# logic_qspi.net
KiCad netlist of a schematic drawn in Altium Designer
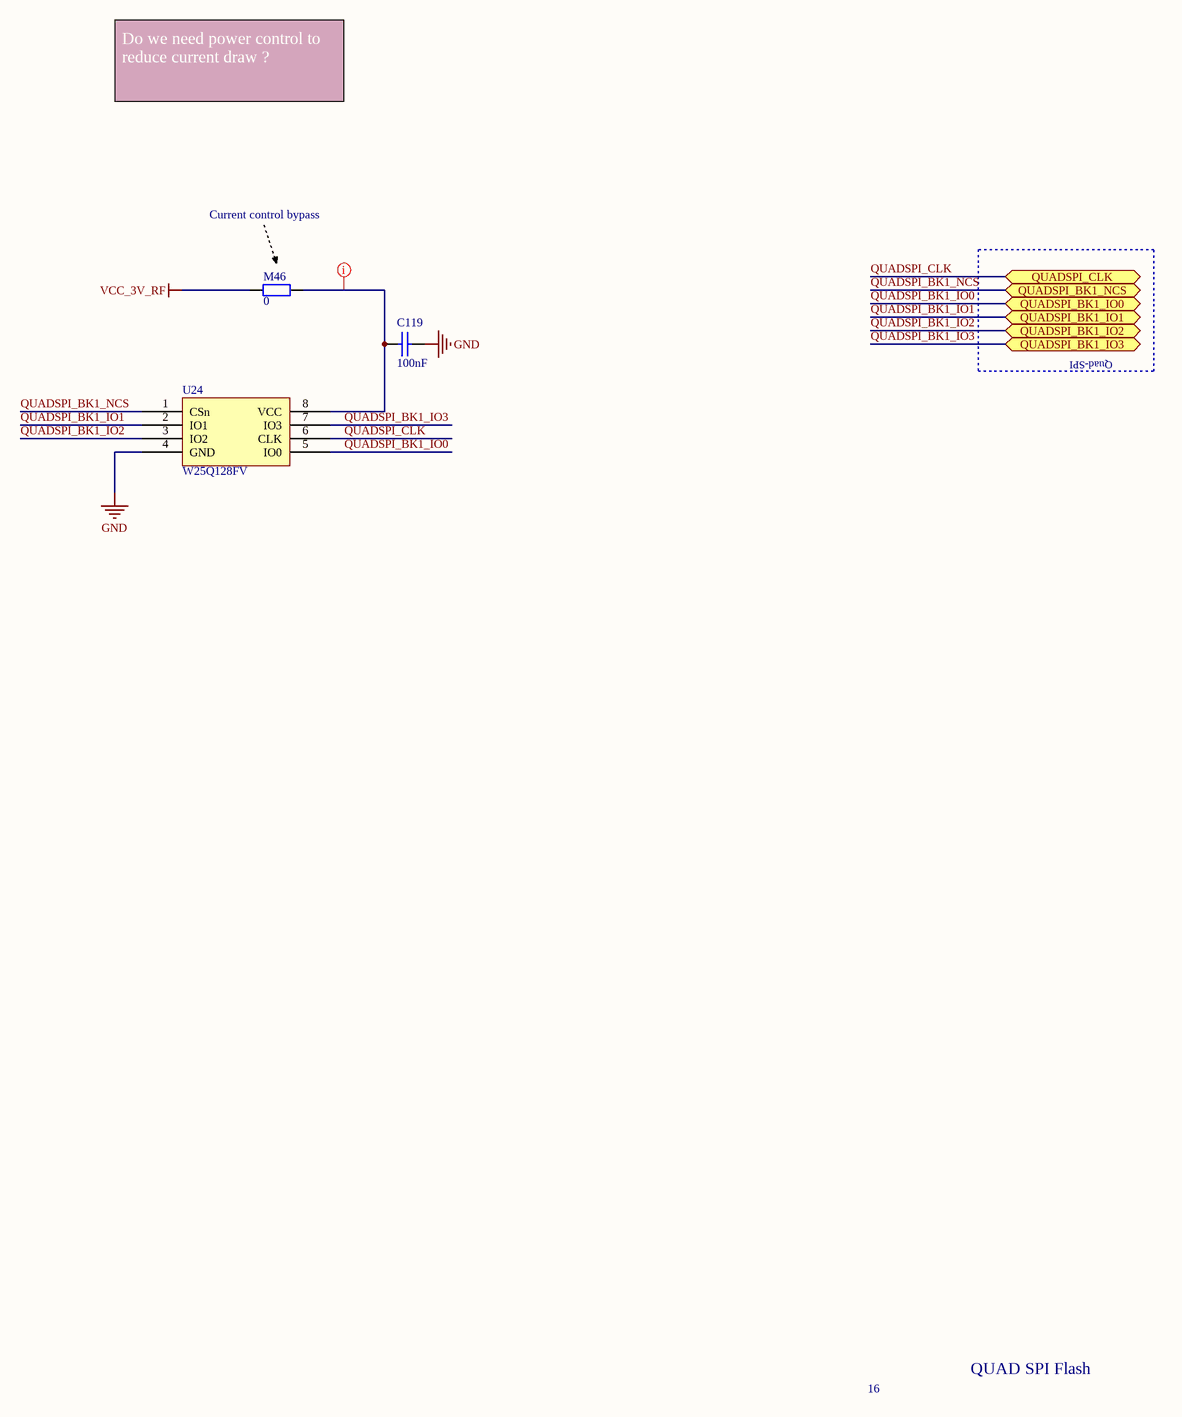
[diagram p0: logic_qspi.SchDoc]

(export (version "E")
  (design (tool "Eeschema 10.0.6"))
  (components
    (comp (ref "C119")
      (value "100nF")
      (footprint "0805")
      (description "Capacitor")
      (libsource (lib "mcHF_ui") (part "CAP"))
    )
    (comp (ref "M46")
      (value "0")
      (footprint "0805")
      (description "Resistor")
      (libsource (lib "mcHF_rf") (part "RES"))
    )
    (comp (ref "U24")
      (value "W25Q128FV")
      (footprint "SOIC8_208MIL")
      (description "3V 128Mbit QUAD SPI")
      (libsource (lib "__ui") (part "W25Q128FV"))
    )
  )
  (nets
    (net (code "1") (name "/QUADSPI_BK1_IO0") (class "Default")
      (node (ref "U24") (pin "5") (pinfunction "IO0_5") (pintype "passive"))
    )
    (net (code "2") (name "/QUADSPI_BK1_IO1") (class "Default")
      (node (ref "U24") (pin "2") (pinfunction "IO1_2") (pintype "passive"))
    )
    (net (code "3") (name "/QUADSPI_BK1_IO2") (class "Default")
      (node (ref "U24") (pin "3") (pinfunction "IO2_3") (pintype "passive"))
    )
    (net (code "4") (name "/QUADSPI_BK1_IO3") (class "Default")
      (node (ref "U24") (pin "7") (pinfunction "IO3_7") (pintype "passive"))
    )
    (net (code "5") (name "/QUADSPI_BK1_NCS") (class "Default")
      (node (ref "U24") (pin "1") (pinfunction "CSn_1") (pintype "passive"))
    )
    (net (code "6") (name "/QUADSPI_CLK") (class "Default")
      (node (ref "U24") (pin "6") (pinfunction "CLK_6") (pintype "passive"))
    )
    (net (code "7") (name "GND") (class "Default")
      (node (ref "C119") (pin "2") (pinfunction "2_2") (pintype "passive"))
      (node (ref "U24") (pin "4") (pinfunction "GND_4") (pintype "passive"))
    )
    (net (code "8") (name "Net-(U24-VCC)") (class "Default")
      (node (ref "C119") (pin "1") (pinfunction "1_1") (pintype "passive"))
      (node (ref "M46") (pin "2") (pinfunction "2_2") (pintype "passive"))
      (node (ref "U24") (pin "8") (pinfunction "VCC_8") (pintype "passive"))
    )
    (net (code "9") (name "VCC_3V_RF") (class "Default")
      (node (ref "M46") (pin "1") (pinfunction "1_1") (pintype "passive"))
    )
  )
)
